# L1Demoscene.net
KiCad netlist of a schematic drawn in EAGLE
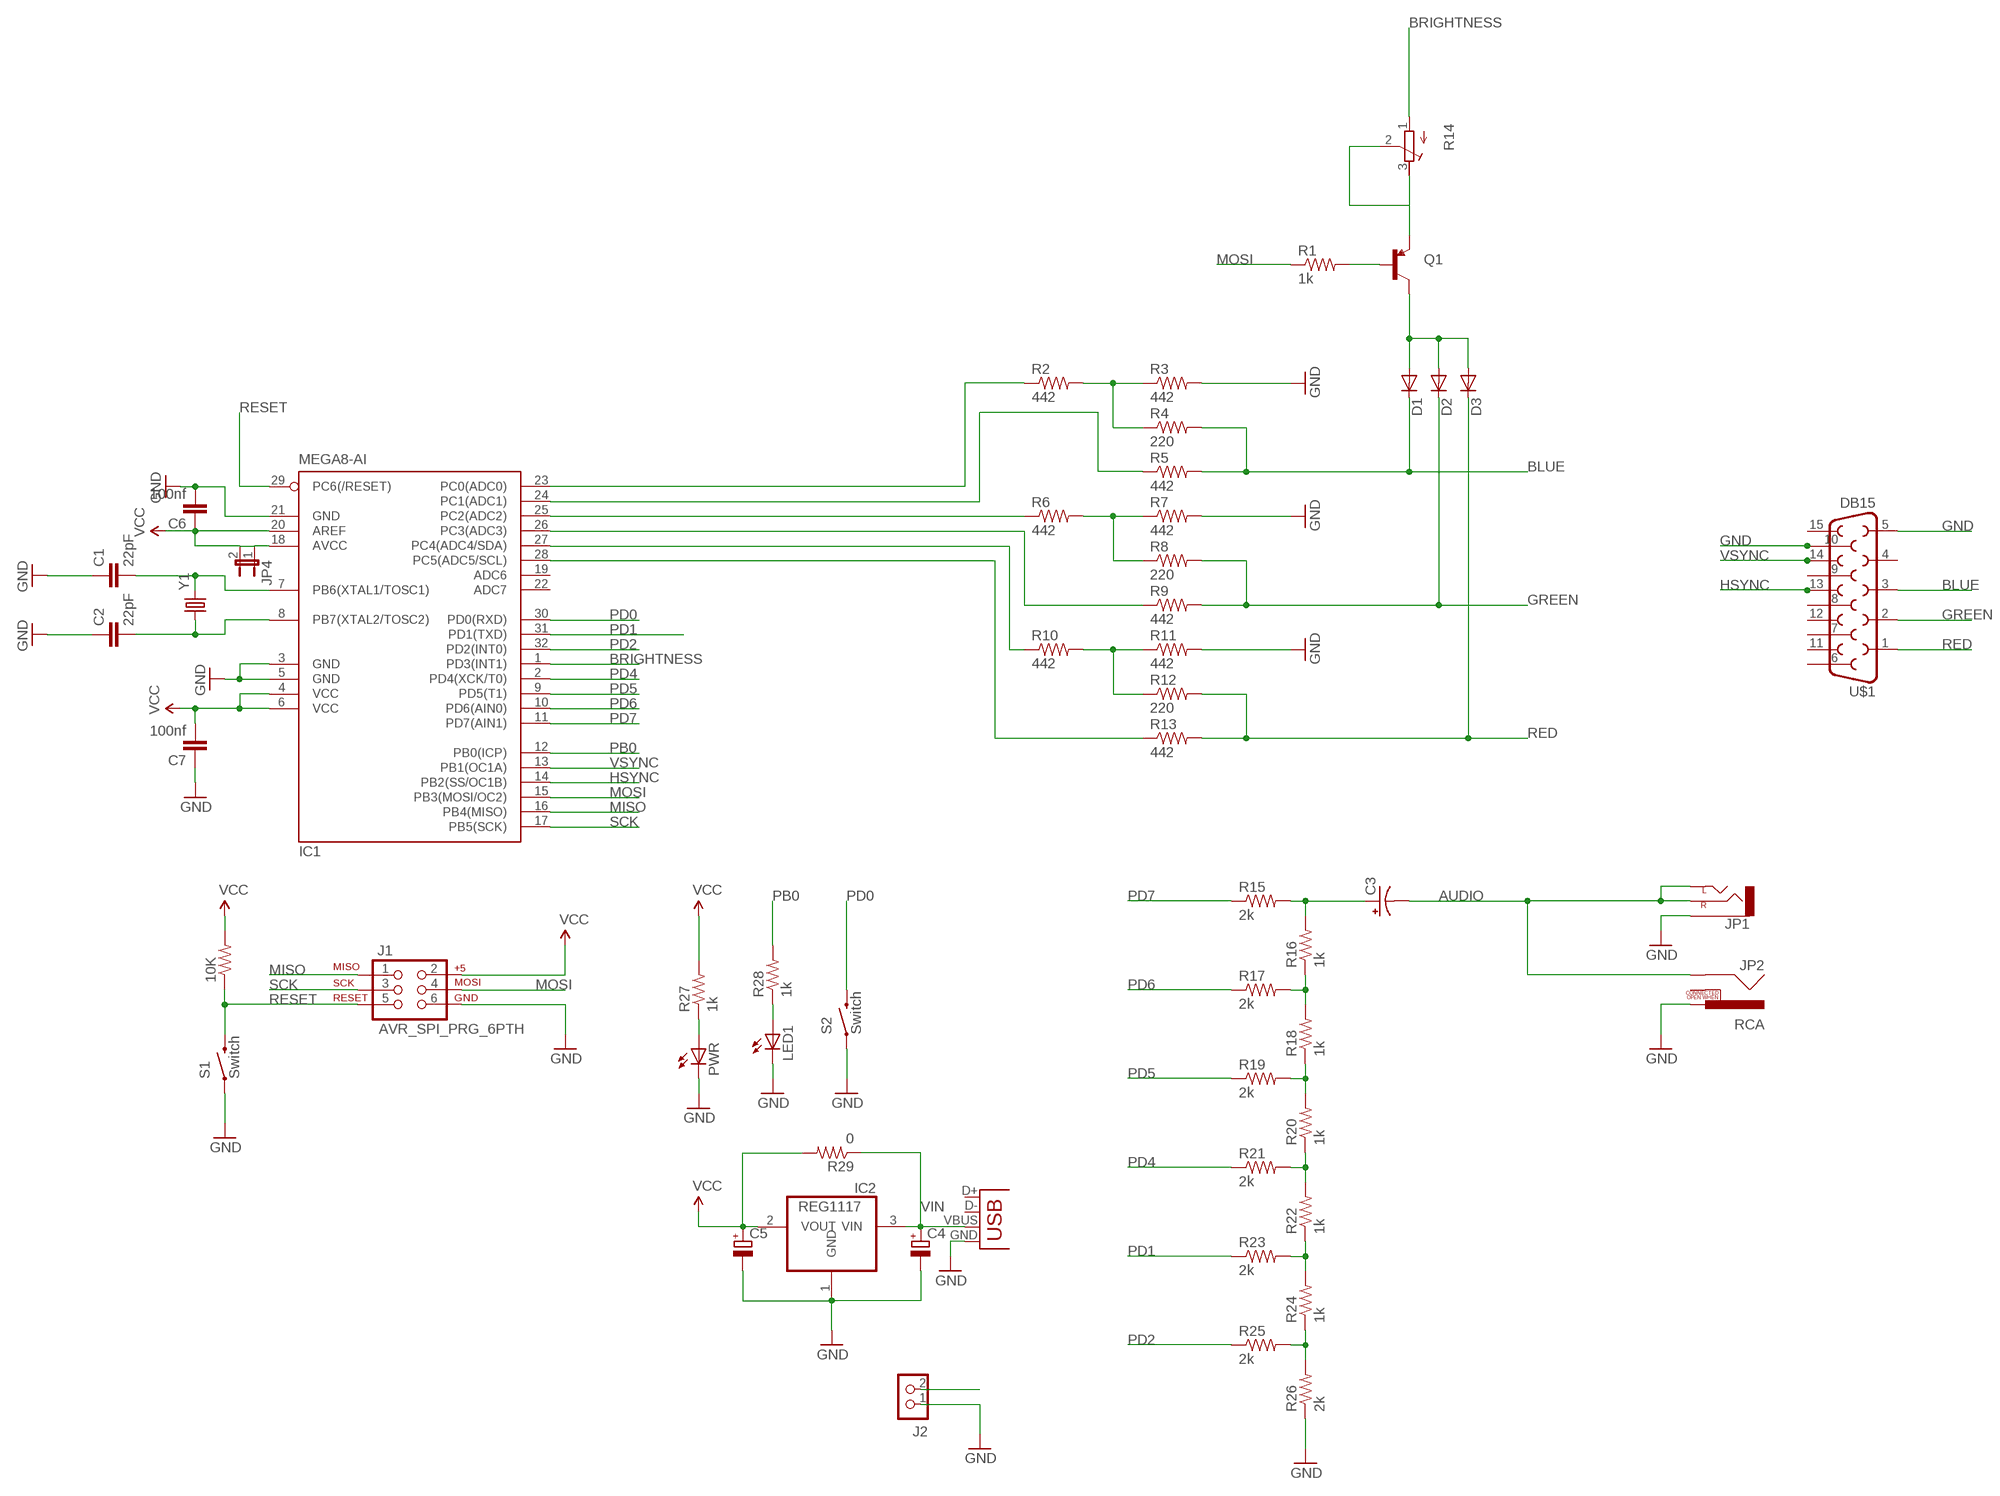
[diagram p0: schematic, sheet 1]

(export (version "E")
  (design (tool "Eeschema 10.0.6"))
  (components
    (comp (ref "10K")
      (value "RESISTOR0603-RES")
      (footprint "eagle-import:0603-RES")
      (libsource (lib "eagle-import") (part "RESISTOR0603-RES"))
    )
    (comp (ref "C1")
      (value "22pF")
      (footprint "eagle-import:0603-CAP")
      (libsource (lib "eagle-import") (part "CAP0603-CAP"))
    )
    (comp (ref "C2")
      (value "22pF")
      (footprint "eagle-import:0603-CAP")
      (libsource (lib "eagle-import") (part "CAP0603-CAP"))
    )
    (comp (ref "C3")
      (value "CAP_POL1206")
      (footprint "eagle-import:EIA3216")
      (libsource (lib "eagle-import") (part "CAP_POL1206"))
    )
    (comp (ref "C4")
      (value "CAPACITOR_POL-SMC_A")
      (footprint "eagle-import:SMC_A")
      (libsource (lib "eagle-import") (part "CAPACITOR_POL-SMC_A"))
    )
    (comp (ref "C5")
      (value "CAPACITOR_POL-SMC_A")
      (footprint "eagle-import:SMC_A")
      (libsource (lib "eagle-import") (part "CAPACITOR_POL-SMC_A"))
    )
    (comp (ref "C6")
      (value "100nf")
      (footprint "eagle-import:0603-CAP")
      (libsource (lib "eagle-import") (part "CAP0603-CAP"))
    )
    (comp (ref "C7")
      (value "100nf")
      (footprint "eagle-import:0603-CAP")
      (libsource (lib "eagle-import") (part "CAP0603-CAP"))
    )
    (comp (ref "D1")
      (value "DIODESOD")
      (footprint "eagle-import:SOD-323")
      (libsource (lib "eagle-import") (part "DIODESOD"))
    )
    (comp (ref "D2")
      (value "DIODESOD")
      (footprint "eagle-import:SOD-323")
      (libsource (lib "eagle-import") (part "DIODESOD"))
    )
    (comp (ref "D3")
      (value "DIODESOD")
      (footprint "eagle-import:SOD-323")
      (libsource (lib "eagle-import") (part "DIODESOD"))
    )
    (comp (ref "IC1")
      (value "MEGA8-AI")
      (footprint "eagle-import:TQFP32-08")
      (fields (field (name "MPN") "ATMEGA8-16AU"))
      (libsource (lib "eagle-import") (part "MEGA8-AI"))
    )
    (comp (ref "IC2")
      (value "REG1117")
      (footprint "eagle-import:SOT223")
      (libsource (lib "eagle-import") (part "REG1117"))
    )
    (comp (ref "J1")
      (value "AVR_SPI_PRG_6PTH")
      (footprint "eagle-import:2X3")
      (libsource (lib "eagle-import") (part "AVR_SPI_PRG_6PTH"))
    )
    (comp (ref "J2")
      (value "CON_HEADER_1X02-PTH")
      (footprint "eagle-import:M1X2")
      (libsource (lib "eagle-import") (part "CON_HEADER_1X02-PTH"))
    )
    (comp (ref "JP1")
      (value "AUDIO-JACKPTH")
      (footprint "eagle-import:AUDIO-JACK")
      (libsource (lib "eagle-import") (part "AUDIO-JACKPTH"))
    )
    (comp (ref "JP2")
      (value "RCA")
      (footprint "eagle-import:RCA")
      (libsource (lib "eagle-import") (part "RCA"))
    )
    (comp (ref "JP3")
      (value "USB-MICROB")
      (footprint "eagle-import:USB-MICROB")
      (libsource (lib "eagle-import") (part "USB-MICROB"))
    )
    (comp (ref "JP4")
      (value "JUMPER-2SMD-NC")
      (footprint "eagle-import:SJ_2S")
      (libsource (lib "eagle-import") (part "JUMPER-2SMD-NC"))
    )
    (comp (ref "LED1")
      (value "LED-0603")
      (footprint "eagle-import:LED-603")
      (libsource (lib "eagle-import") (part "LED-0603"))
    )
    (comp (ref "PWR")
      (value "LED-0603")
      (footprint "eagle-import:LED-603")
      (libsource (lib "eagle-import") (part "LED-0603"))
    )
    (comp (ref "Q1")
      (value "TRANSISTOR_PNPSMD")
      (footprint "eagle-import:SOT23-3")
      (libsource (lib "eagle-import") (part "TRANSISTOR_PNPSMD"))
    )
    (comp (ref "R1")
      (value "1k")
      (footprint "eagle-import:0603-RES")
      (libsource (lib "eagle-import") (part "RESISTOR0603-RES"))
    )
    (comp (ref "R2")
      (value "442")
      (footprint "eagle-import:0603-RES")
      (libsource (lib "eagle-import") (part "RESISTOR0603-RES"))
    )
    (comp (ref "R3")
      (value "442")
      (footprint "eagle-import:0603-RES")
      (libsource (lib "eagle-import") (part "RESISTOR0603-RES"))
    )
    (comp (ref "R4")
      (value "220")
      (footprint "eagle-import:0603-RES")
      (libsource (lib "eagle-import") (part "RESISTOR0603-RES"))
    )
    (comp (ref "R5")
      (value "442")
      (footprint "eagle-import:0603-RES")
      (libsource (lib "eagle-import") (part "RESISTOR0603-RES"))
    )
    (comp (ref "R6")
      (value "442")
      (footprint "eagle-import:0603-RES")
      (libsource (lib "eagle-import") (part "RESISTOR0603-RES"))
    )
    (comp (ref "R7")
      (value "442")
      (footprint "eagle-import:0603-RES")
      (libsource (lib "eagle-import") (part "RESISTOR0603-RES"))
    )
    (comp (ref "R8")
      (value "220")
      (footprint "eagle-import:0603-RES")
      (libsource (lib "eagle-import") (part "RESISTOR0603-RES"))
    )
    (comp (ref "R9")
      (value "442")
      (footprint "eagle-import:0603-RES")
      (libsource (lib "eagle-import") (part "RESISTOR0603-RES"))
    )
    (comp (ref "R10")
      (value "442")
      (footprint "eagle-import:0603-RES")
      (libsource (lib "eagle-import") (part "RESISTOR0603-RES"))
    )
    (comp (ref "R11")
      (value "442")
      (footprint "eagle-import:0603-RES")
      (libsource (lib "eagle-import") (part "RESISTOR0603-RES"))
    )
    (comp (ref "R12")
      (value "220")
      (footprint "eagle-import:0603-RES")
      (libsource (lib "eagle-import") (part "RESISTOR0603-RES"))
    )
    (comp (ref "R13")
      (value "442")
      (footprint "eagle-import:0603-RES")
      (libsource (lib "eagle-import") (part "RESISTOR0603-RES"))
    )
    (comp (ref "R14")
      (value "R-TRIMM3296W")
      (footprint "eagle-import:RTRIM3296W")
      (libsource (lib "eagle-import") (part "R-TRIMM3296W"))
    )
    (comp (ref "R15")
      (value "2k")
      (footprint "eagle-import:0603-RES")
      (libsource (lib "eagle-import") (part "RESISTOR0603-RES"))
    )
    (comp (ref "R16")
      (value "1k")
      (footprint "eagle-import:0603-RES")
      (libsource (lib "eagle-import") (part "RESISTOR0603-RES"))
    )
    (comp (ref "R17")
      (value "2k")
      (footprint "eagle-import:0603-RES")
      (libsource (lib "eagle-import") (part "RESISTOR0603-RES"))
    )
    (comp (ref "R18")
      (value "1k")
      (footprint "eagle-import:0603-RES")
      (libsource (lib "eagle-import") (part "RESISTOR0603-RES"))
    )
    (comp (ref "R19")
      (value "2k")
      (footprint "eagle-import:0603-RES")
      (libsource (lib "eagle-import") (part "RESISTOR0603-RES"))
    )
    (comp (ref "R20")
      (value "1k")
      (footprint "eagle-import:0603-RES")
      (libsource (lib "eagle-import") (part "RESISTOR0603-RES"))
    )
    (comp (ref "R21")
      (value "2k")
      (footprint "eagle-import:0603-RES")
      (libsource (lib "eagle-import") (part "RESISTOR0603-RES"))
    )
    (comp (ref "R22")
      (value "1k")
      (footprint "eagle-import:0603-RES")
      (libsource (lib "eagle-import") (part "RESISTOR0603-RES"))
    )
    (comp (ref "R23")
      (value "2k")
      (footprint "eagle-import:0603-RES")
      (libsource (lib "eagle-import") (part "RESISTOR0603-RES"))
    )
    (comp (ref "R24")
      (value "1k")
      (footprint "eagle-import:0603-RES")
      (libsource (lib "eagle-import") (part "RESISTOR0603-RES"))
    )
    (comp (ref "R25")
      (value "2k")
      (footprint "eagle-import:0603-RES")
      (libsource (lib "eagle-import") (part "RESISTOR0603-RES"))
    )
    (comp (ref "R26")
      (value "2k")
      (footprint "eagle-import:0603-RES")
      (libsource (lib "eagle-import") (part "RESISTOR0603-RES"))
    )
    (comp (ref "R27")
      (value "1k")
      (footprint "eagle-import:0603-RES")
      (libsource (lib "eagle-import") (part "RESISTOR0603-RES"))
    )
    (comp (ref "R28")
      (value "1k")
      (footprint "eagle-import:0603-RES")
      (libsource (lib "eagle-import") (part "RESISTOR0603-RES"))
    )
    (comp (ref "R29")
      (value "0")
      (footprint "eagle-import:1206")
      (libsource (lib "eagle-import") (part "RESISTOR1206"))
    )
    (comp (ref "S1")
      (value "Switch")
      (footprint "eagle-import:SPARKFUN-ELECTROMECHANICAL_TACTILE-SWITCH-1101NE")
      (libsource (lib "eagle-import") (part "SPARKFUN-ELECTROMECHANICAL_SWITCH-MOMENTARY-2-SMD-1101NE"))
    )
    (comp (ref "S2")
      (value "Switch")
      (footprint "eagle-import:SPARKFUN-ELECTROMECHANICAL_TACTILE-SWITCH-1101NE")
      (libsource (lib "eagle-import") (part "SPARKFUN-ELECTROMECHANICAL_SWITCH-MOMENTARY-2-SMD-1101NE"))
    )
    (comp (ref "U$1")
      (value "DB15")
      (footprint "eagle-import:DB15")
      (libsource (lib "eagle-import") (part "DB15"))
    )
    (comp (ref "Y1")
      (value "CRYSTALHC49US")
      (footprint "eagle-import:HC49US")
      (libsource (lib "eagle-import") (part "CRYSTALHC49US"))
    )
  )
  (nets
    (net (code "1") (name "AUDIO") (class "Default")
      (node (ref "C3") (pin "C") (pinfunction "-_C") (pintype "passive"))
      (node (ref "JP1") (pin "RING") (pinfunction "RIGHT_RING") (pintype "bidirectional"))
      (node (ref "JP1") (pin "TIP") (pinfunction "LEFT_TIP") (pintype "bidirectional"))
      (node (ref "JP2") (pin "SHELL") (pinfunction "SHELL_SHELL") (pintype "bidirectional"))
    )
    (net (code "2") (name "BLUE") (class "Default")
      (node (ref "D1") (pin "1") (pinfunction "C_1") (pintype "passive"))
      (node (ref "R4") (pin "2") (pinfunction "2_2") (pintype "passive"))
      (node (ref "R5") (pin "2") (pinfunction "2_2") (pintype "passive"))
      (node (ref "U$1") (pin "3") (pinfunction "3_3") (pintype "passive"))
    )
    (net (code "3") (name "BRIGHTNESS") (class "Default")
      (node (ref "IC1") (pin "1") (pinfunction "PD3(INT1)_1") (pintype "bidirectional"))
      (node (ref "R14") (pin "1") (pinfunction "A_1") (pintype "passive"))
    )
    (net (code "4") (name "GND") (class "Default")
      (node (ref "C1") (pin "1") (pinfunction "1_1") (pintype "passive"))
      (node (ref "C2") (pin "1") (pinfunction "1_1") (pintype "passive"))
      (node (ref "C4") (pin "-") (pinfunction "-_-") (pintype "passive"))
      (node (ref "C5") (pin "-") (pinfunction "-_-") (pintype "passive"))
      (node (ref "C6") (pin "2") (pinfunction "2_2") (pintype "passive"))
      (node (ref "C7") (pin "1") (pinfunction "1_1") (pintype "passive"))
      (node (ref "IC1") (pin "21") (pinfunction "GND_21") (pintype "power_in"))
      (node (ref "IC1") (pin "3") (pinfunction "GND_3") (pintype "power_in"))
      (node (ref "IC1") (pin "5") (pinfunction "GND_5") (pintype "power_in"))
      (node (ref "IC2") (pin "1") (pinfunction "GND_1") (pintype "power_in"))
      (node (ref "J1") (pin "6") (pinfunction "6_6") (pintype "passive"))
      (node (ref "J2") (pin "1") (pinfunction "1_1") (pintype "passive"))
      (node (ref "JP1") (pin "SLEEVE") (pinfunction "SLEEVE_SLEEVE") (pintype "bidirectional"))
      (node (ref "JP2") (pin "PIN") (pinfunction "PIN_PIN") (pintype "bidirectional"))
      (node (ref "JP3") (pin "GND") (pinfunction "GND_GND") (pintype "bidirectional"))
      (node (ref "LED1") (pin "C") (pinfunction "C_C") (pintype "passive"))
      (node (ref "PWR") (pin "C") (pinfunction "C_C") (pintype "passive"))
      (node (ref "R11") (pin "2") (pinfunction "2_2") (pintype "passive"))
      (node (ref "R26") (pin "1") (pinfunction "1_1") (pintype "passive"))
      (node (ref "R3") (pin "2") (pinfunction "2_2") (pintype "passive"))
      (node (ref "R7") (pin "2") (pinfunction "2_2") (pintype "passive"))
      (node (ref "S1") (pin "P$1") (pinfunction "1_P$1") (pintype "passive"))
      (node (ref "S2") (pin "P$1") (pinfunction "1_P$1") (pintype "passive"))
      (node (ref "U$1") (pin "10") (pinfunction "10_10") (pintype "passive"))
      (node (ref "U$1") (pin "5") (pinfunction "5_5") (pintype "passive"))
    )
    (net (code "5") (name "GREEN") (class "Default")
      (node (ref "D2") (pin "1") (pinfunction "C_1") (pintype "passive"))
      (node (ref "R8") (pin "2") (pinfunction "2_2") (pintype "passive"))
      (node (ref "R9") (pin "2") (pinfunction "2_2") (pintype "passive"))
      (node (ref "U$1") (pin "2") (pinfunction "2_2") (pintype "passive"))
    )
    (net (code "6") (name "HSYNC") (class "Default")
      (node (ref "IC1") (pin "14") (pinfunction "PB2(SS/OC1B)_14") (pintype "bidirectional"))
      (node (ref "U$1") (pin "13") (pinfunction "13_13") (pintype "passive"))
    )
    (net (code "7") (name "MISO") (class "Default")
      (node (ref "IC1") (pin "16") (pinfunction "PB4(MISO)_16") (pintype "bidirectional"))
      (node (ref "J1") (pin "1") (pinfunction "1_1") (pintype "passive"))
    )
    (net (code "8") (name "MOSI") (class "Default")
      (node (ref "IC1") (pin "15") (pinfunction "PB3(MOSI/OC2)_15") (pintype "bidirectional"))
      (node (ref "J1") (pin "4") (pinfunction "4_4") (pintype "passive"))
      (node (ref "R1") (pin "1") (pinfunction "1_1") (pintype "passive"))
    )
    (net (code "9") (name "Net-(C3-+)") (class "Default")
      (node (ref "C3") (pin "A") (pinfunction "+_A") (pintype "passive"))
      (node (ref "R15") (pin "2") (pinfunction "2_2") (pintype "passive"))
      (node (ref "R16") (pin "2") (pinfunction "2_2") (pintype "passive"))
    )
    (net (code "10") (name "Net-(D1-A)") (class "Default")
      (node (ref "D1") (pin "2") (pinfunction "A_2") (pintype "passive"))
      (node (ref "D2") (pin "2") (pinfunction "A_2") (pintype "passive"))
      (node (ref "D3") (pin "2") (pinfunction "A_2") (pintype "passive"))
      (node (ref "Q1") (pin "3") (pinfunction "C_3") (pintype "passive"))
    )
    (net (code "11") (name "Net-(IC1-PB6(XTAL1{slash}TOSC1))") (class "Default")
      (node (ref "C1") (pin "2") (pinfunction "2_2") (pintype "passive"))
      (node (ref "IC1") (pin "7") (pinfunction "PB6(XTAL1/TOSC1)_7") (pintype "bidirectional"))
      (node (ref "Y1") (pin "2") (pinfunction "2_2") (pintype "passive"))
    )
    (net (code "12") (name "Net-(IC1-PB7(XTAL2{slash}TOSC2))") (class "Default")
      (node (ref "C2") (pin "2") (pinfunction "2_2") (pintype "passive"))
      (node (ref "IC1") (pin "8") (pinfunction "PB7(XTAL2/TOSC2)_8") (pintype "bidirectional"))
      (node (ref "Y1") (pin "1") (pinfunction "1_1") (pintype "passive"))
    )
    (net (code "13") (name "Net-(IC1-PC0(ADC0))") (class "Default")
      (node (ref "IC1") (pin "23") (pinfunction "PC0(ADC0)_23") (pintype "bidirectional"))
      (node (ref "R2") (pin "1") (pinfunction "1_1") (pintype "passive"))
    )
    (net (code "14") (name "Net-(IC1-PC1(ADC1))") (class "Default")
      (node (ref "IC1") (pin "24") (pinfunction "PC1(ADC1)_24") (pintype "bidirectional"))
      (node (ref "R5") (pin "1") (pinfunction "1_1") (pintype "passive"))
    )
    (net (code "15") (name "Net-(IC1-PC2(ADC2))") (class "Default")
      (node (ref "IC1") (pin "25") (pinfunction "PC2(ADC2)_25") (pintype "bidirectional"))
      (node (ref "R6") (pin "1") (pinfunction "1_1") (pintype "passive"))
    )
    (net (code "16") (name "Net-(IC1-PC3(ADC3))") (class "Default")
      (node (ref "IC1") (pin "26") (pinfunction "PC3(ADC3)_26") (pintype "bidirectional"))
      (node (ref "R9") (pin "1") (pinfunction "1_1") (pintype "passive"))
    )
    (net (code "17") (name "Net-(IC1-PC4(ADC4{slash}SDA))") (class "Default")
      (node (ref "IC1") (pin "27") (pinfunction "PC4(ADC4/SDA)_27") (pintype "bidirectional"))
      (node (ref "R10") (pin "1") (pinfunction "1_1") (pintype "passive"))
    )
    (net (code "18") (name "Net-(IC1-PC5(ADC5{slash}SCL))") (class "Default")
      (node (ref "IC1") (pin "28") (pinfunction "PC5(ADC5/SCL)_28") (pintype "bidirectional"))
      (node (ref "R13") (pin "1") (pinfunction "1_1") (pintype "passive"))
    )
    (net (code "19") (name "Net-(LED1-PadA)") (class "Default")
      (node (ref "LED1") (pin "A") (pinfunction "A_A") (pintype "passive"))
      (node (ref "R28") (pin "1") (pinfunction "1_1") (pintype "passive"))
    )
    (net (code "20") (name "Net-(PWR-PadA)") (class "Default")
      (node (ref "PWR") (pin "A") (pinfunction "A_A") (pintype "passive"))
      (node (ref "R27") (pin "1") (pinfunction "1_1") (pintype "passive"))
    )
    (net (code "21") (name "Net-(Q1-B)") (class "Default")
      (node (ref "Q1") (pin "1") (pinfunction "B_1") (pintype "passive"))
      (node (ref "R1") (pin "2") (pinfunction "2_2") (pintype "passive"))
    )
    (net (code "22") (name "Net-(Q1-E)") (class "Default")
      (node (ref "Q1") (pin "2") (pinfunction "E_2") (pintype "passive"))
      (node (ref "R14") (pin "2") (pinfunction "S_2") (pintype "passive"))
      (node (ref "R14") (pin "3") (pinfunction "E_3") (pintype "passive"))
    )
    (net (code "23") (name "Net-(R2-Pad2)") (class "Default")
      (node (ref "R2") (pin "2") (pinfunction "2_2") (pintype "passive"))
      (node (ref "R3") (pin "1") (pinfunction "1_1") (pintype "passive"))
      (node (ref "R4") (pin "1") (pinfunction "1_1") (pintype "passive"))
    )
    (net (code "24") (name "Net-(R6-Pad2)") (class "Default")
      (node (ref "R6") (pin "2") (pinfunction "2_2") (pintype "passive"))
      (node (ref "R7") (pin "1") (pinfunction "1_1") (pintype "passive"))
      (node (ref "R8") (pin "1") (pinfunction "1_1") (pintype "passive"))
    )
    (net (code "25") (name "Net-(R10-Pad2)") (class "Default")
      (node (ref "R10") (pin "2") (pinfunction "2_2") (pintype "passive"))
      (node (ref "R11") (pin "1") (pinfunction "1_1") (pintype "passive"))
      (node (ref "R12") (pin "1") (pinfunction "1_1") (pintype "passive"))
    )
    (net (code "26") (name "Net-(R16-Pad1)") (class "Default")
      (node (ref "R16") (pin "1") (pinfunction "1_1") (pintype "passive"))
      (node (ref "R17") (pin "2") (pinfunction "2_2") (pintype "passive"))
      (node (ref "R18") (pin "2") (pinfunction "2_2") (pintype "passive"))
    )
    (net (code "27") (name "Net-(R18-Pad1)") (class "Default")
      (node (ref "R18") (pin "1") (pinfunction "1_1") (pintype "passive"))
      (node (ref "R19") (pin "2") (pinfunction "2_2") (pintype "passive"))
      (node (ref "R20") (pin "2") (pinfunction "2_2") (pintype "passive"))
    )
    (net (code "28") (name "Net-(R20-Pad1)") (class "Default")
      (node (ref "R20") (pin "1") (pinfunction "1_1") (pintype "passive"))
      (node (ref "R21") (pin "2") (pinfunction "2_2") (pintype "passive"))
      (node (ref "R22") (pin "2") (pinfunction "2_2") (pintype "passive"))
    )
    (net (code "29") (name "Net-(R22-Pad1)") (class "Default")
      (node (ref "R22") (pin "1") (pinfunction "1_1") (pintype "passive"))
      (node (ref "R23") (pin "2") (pinfunction "2_2") (pintype "passive"))
      (node (ref "R24") (pin "2") (pinfunction "2_2") (pintype "passive"))
    )
    (net (code "30") (name "Net-(R24-Pad1)") (class "Default")
      (node (ref "R24") (pin "1") (pinfunction "1_1") (pintype "passive"))
      (node (ref "R25") (pin "2") (pinfunction "2_2") (pintype "passive"))
      (node (ref "R26") (pin "2") (pinfunction "2_2") (pintype "passive"))
    )
    (net (code "31") (name "PB0") (class "Default")
      (node (ref "IC1") (pin "12") (pinfunction "PB0(ICP)_12") (pintype "bidirectional"))
      (node (ref "R28") (pin "2") (pinfunction "2_2") (pintype "passive"))
    )
    (net (code "32") (name "PD0") (class "Default")
      (node (ref "IC1") (pin "30") (pinfunction "PD0(RXD)_30") (pintype "bidirectional"))
      (node (ref "S2") (pin "P$2") (pinfunction "2_P$2") (pintype "passive"))
    )
    (net (code "33") (name "PD1") (class "Default")
      (node (ref "IC1") (pin "31") (pinfunction "PD1(TXD)_31") (pintype "bidirectional"))
      (node (ref "R23") (pin "1") (pinfunction "1_1") (pintype "passive"))
    )
    (net (code "34") (name "PD2") (class "Default")
      (node (ref "IC1") (pin "32") (pinfunction "PD2(INT0)_32") (pintype "bidirectional"))
      (node (ref "R25") (pin "1") (pinfunction "1_1") (pintype "passive"))
    )
    (net (code "35") (name "PD4") (class "Default")
      (node (ref "IC1") (pin "2") (pinfunction "PD4(XCK/T0)_2") (pintype "bidirectional"))
      (node (ref "R21") (pin "1") (pinfunction "1_1") (pintype "passive"))
    )
    (net (code "36") (name "PD5") (class "Default")
      (node (ref "IC1") (pin "9") (pinfunction "PD5(T1)_9") (pintype "bidirectional"))
      (node (ref "R19") (pin "1") (pinfunction "1_1") (pintype "passive"))
    )
    (net (code "37") (name "PD6") (class "Default")
      (node (ref "IC1") (pin "10") (pinfunction "PD6(AIN0)_10") (pintype "bidirectional"))
      (node (ref "R17") (pin "1") (pinfunction "1_1") (pintype "passive"))
    )
    (net (code "38") (name "PD7") (class "Default")
      (node (ref "IC1") (pin "11") (pinfunction "PD7(AIN1)_11") (pintype "bidirectional"))
      (node (ref "R15") (pin "1") (pinfunction "1_1") (pintype "passive"))
    )
    (net (code "39") (name "RED") (class "Default")
      (node (ref "D3") (pin "1") (pinfunction "C_1") (pintype "passive"))
      (node (ref "R12") (pin "2") (pinfunction "2_2") (pintype "passive"))
      (node (ref "R13") (pin "2") (pinfunction "2_2") (pintype "passive"))
      (node (ref "U$1") (pin "1") (pinfunction "1_1") (pintype "passive"))
    )
    (net (code "40") (name "RESET") (class "Default")
      (node (ref "10K") (pin "1") (pinfunction "1_1") (pintype "passive"))
      (node (ref "IC1") (pin "29") (pinfunction "PC6(/RESET)_29") (pintype "bidirectional"))
      (node (ref "J1") (pin "5") (pinfunction "5_5") (pintype "passive"))
      (node (ref "S1") (pin "P$2") (pinfunction "2_P$2") (pintype "passive"))
    )
    (net (code "41") (name "SCK") (class "Default")
      (node (ref "IC1") (pin "17") (pinfunction "PB5(SCK)_17") (pintype "bidirectional"))
      (node (ref "J1") (pin "3") (pinfunction "3_3") (pintype "passive"))
    )
    (net (code "42") (name "VCC") (class "Default")
      (node (ref "10K") (pin "2") (pinfunction "2_2") (pintype "passive"))
      (node (ref "C5") (pin "+") (pinfunction "+_+") (pintype "passive"))
      (node (ref "C6") (pin "1") (pinfunction "1_1") (pintype "passive"))
      (node (ref "C7") (pin "2") (pinfunction "2_2") (pintype "passive"))
      (node (ref "IC1") (pin "18") (pinfunction "AVCC_18") (pintype "power_in"))
      (node (ref "IC1") (pin "20") (pinfunction "AREF_20") (pintype "passive"))
      (node (ref "IC1") (pin "4") (pinfunction "VCC_4") (pintype "power_in"))
      (node (ref "IC1") (pin "6") (pinfunction "VCC_6") (pintype "power_in"))
      (node (ref "IC2") (pin "2") (pinfunction "VOUT_2") (pintype "output"))
      (node (ref "J1") (pin "2") (pinfunction "2_2") (pintype "passive"))
      (node (ref "JP4") (pin "1") (pinfunction "1_1") (pintype "passive"))
      (node (ref "JP4") (pin "2") (pinfunction "2_2") (pintype "passive"))
      (node (ref "R27") (pin "2") (pinfunction "2_2") (pintype "passive"))
      (node (ref "R29") (pin "2") (pinfunction "2_2") (pintype "passive"))
    )
    (net (code "43") (name "VIN") (class "Default")
      (node (ref "C4") (pin "+") (pinfunction "+_+") (pintype "passive"))
      (node (ref "IC2") (pin "3") (pinfunction "VIN_3") (pintype "input"))
      (node (ref "J2") (pin "2") (pinfunction "2_2") (pintype "passive"))
      (node (ref "JP3") (pin "VBUS") (pinfunction "VBUS_VBUS") (pintype "bidirectional"))
      (node (ref "R29") (pin "1") (pinfunction "1_1") (pintype "passive"))
    )
    (net (code "44") (name "VSYNC") (class "Default")
      (node (ref "IC1") (pin "13") (pinfunction "PB1(OC1A)_13") (pintype "bidirectional"))
      (node (ref "U$1") (pin "14") (pinfunction "14_14") (pintype "passive"))
    )
    (net (code "45") (name "unconnected-(IC1-ADC6-Pad19)") (class "Default")
      (node (ref "IC1") (pin "19") (pinfunction "ADC6_19") (pintype "bidirectional"))
    )
    (net (code "46") (name "unconnected-(IC1-ADC7-Pad22)") (class "Default")
      (node (ref "IC1") (pin "22") (pinfunction "ADC7_22") (pintype "bidirectional"))
    )
    (net (code "47") (name "unconnected-(JP2-PadSWITCH)") (class "Default")
      (node (ref "JP2") (pin "SWITCH") (pinfunction "SWITCH_SWITCH") (pintype "bidirectional"))
    )
    (net (code "48") (name "unconnected-(JP3-PadD+)") (class "Default")
      (node (ref "JP3") (pin "D+") (pinfunction "D+_D+") (pintype "bidirectional"))
    )
    (net (code "49") (name "unconnected-(JP3-PadD-)") (class "Default")
      (node (ref "JP3") (pin "D-") (pinfunction "D-_D-") (pintype "bidirectional"))
    )
    (net (code "50") (name "unconnected-(U$1-Pad4)") (class "Default")
      (node (ref "U$1") (pin "4") (pinfunction "4_4") (pintype "passive"))
    )
    (net (code "51") (name "unconnected-(U$1-Pad6)") (class "Default")
      (node (ref "U$1") (pin "6") (pinfunction "6_6") (pintype "passive"))
    )
    (net (code "52") (name "unconnected-(U$1-Pad7)") (class "Default")
      (node (ref "U$1") (pin "7") (pinfunction "7_7") (pintype "passive"))
    )
    (net (code "53") (name "unconnected-(U$1-Pad8)") (class "Default")
      (node (ref "U$1") (pin "8") (pinfunction "8_8") (pintype "passive"))
    )
    (net (code "54") (name "unconnected-(U$1-Pad9)") (class "Default")
      (node (ref "U$1") (pin "9") (pinfunction "9_9") (pintype "passive"))
    )
    (net (code "55") (name "unconnected-(U$1-Pad11)") (class "Default")
      (node (ref "U$1") (pin "11") (pinfunction "11_11") (pintype "passive"))
    )
    (net (code "56") (name "unconnected-(U$1-Pad12)") (class "Default")
      (node (ref "U$1") (pin "12") (pinfunction "12_12") (pintype "passive"))
    )
    (net (code "57") (name "unconnected-(U$1-Pad15)") (class "Default")
      (node (ref "U$1") (pin "15") (pinfunction "15_15") (pintype "passive"))
    )
  )
)
